# PA_Channel.net
KiCad netlist of a schematic drawn in Altium Designer
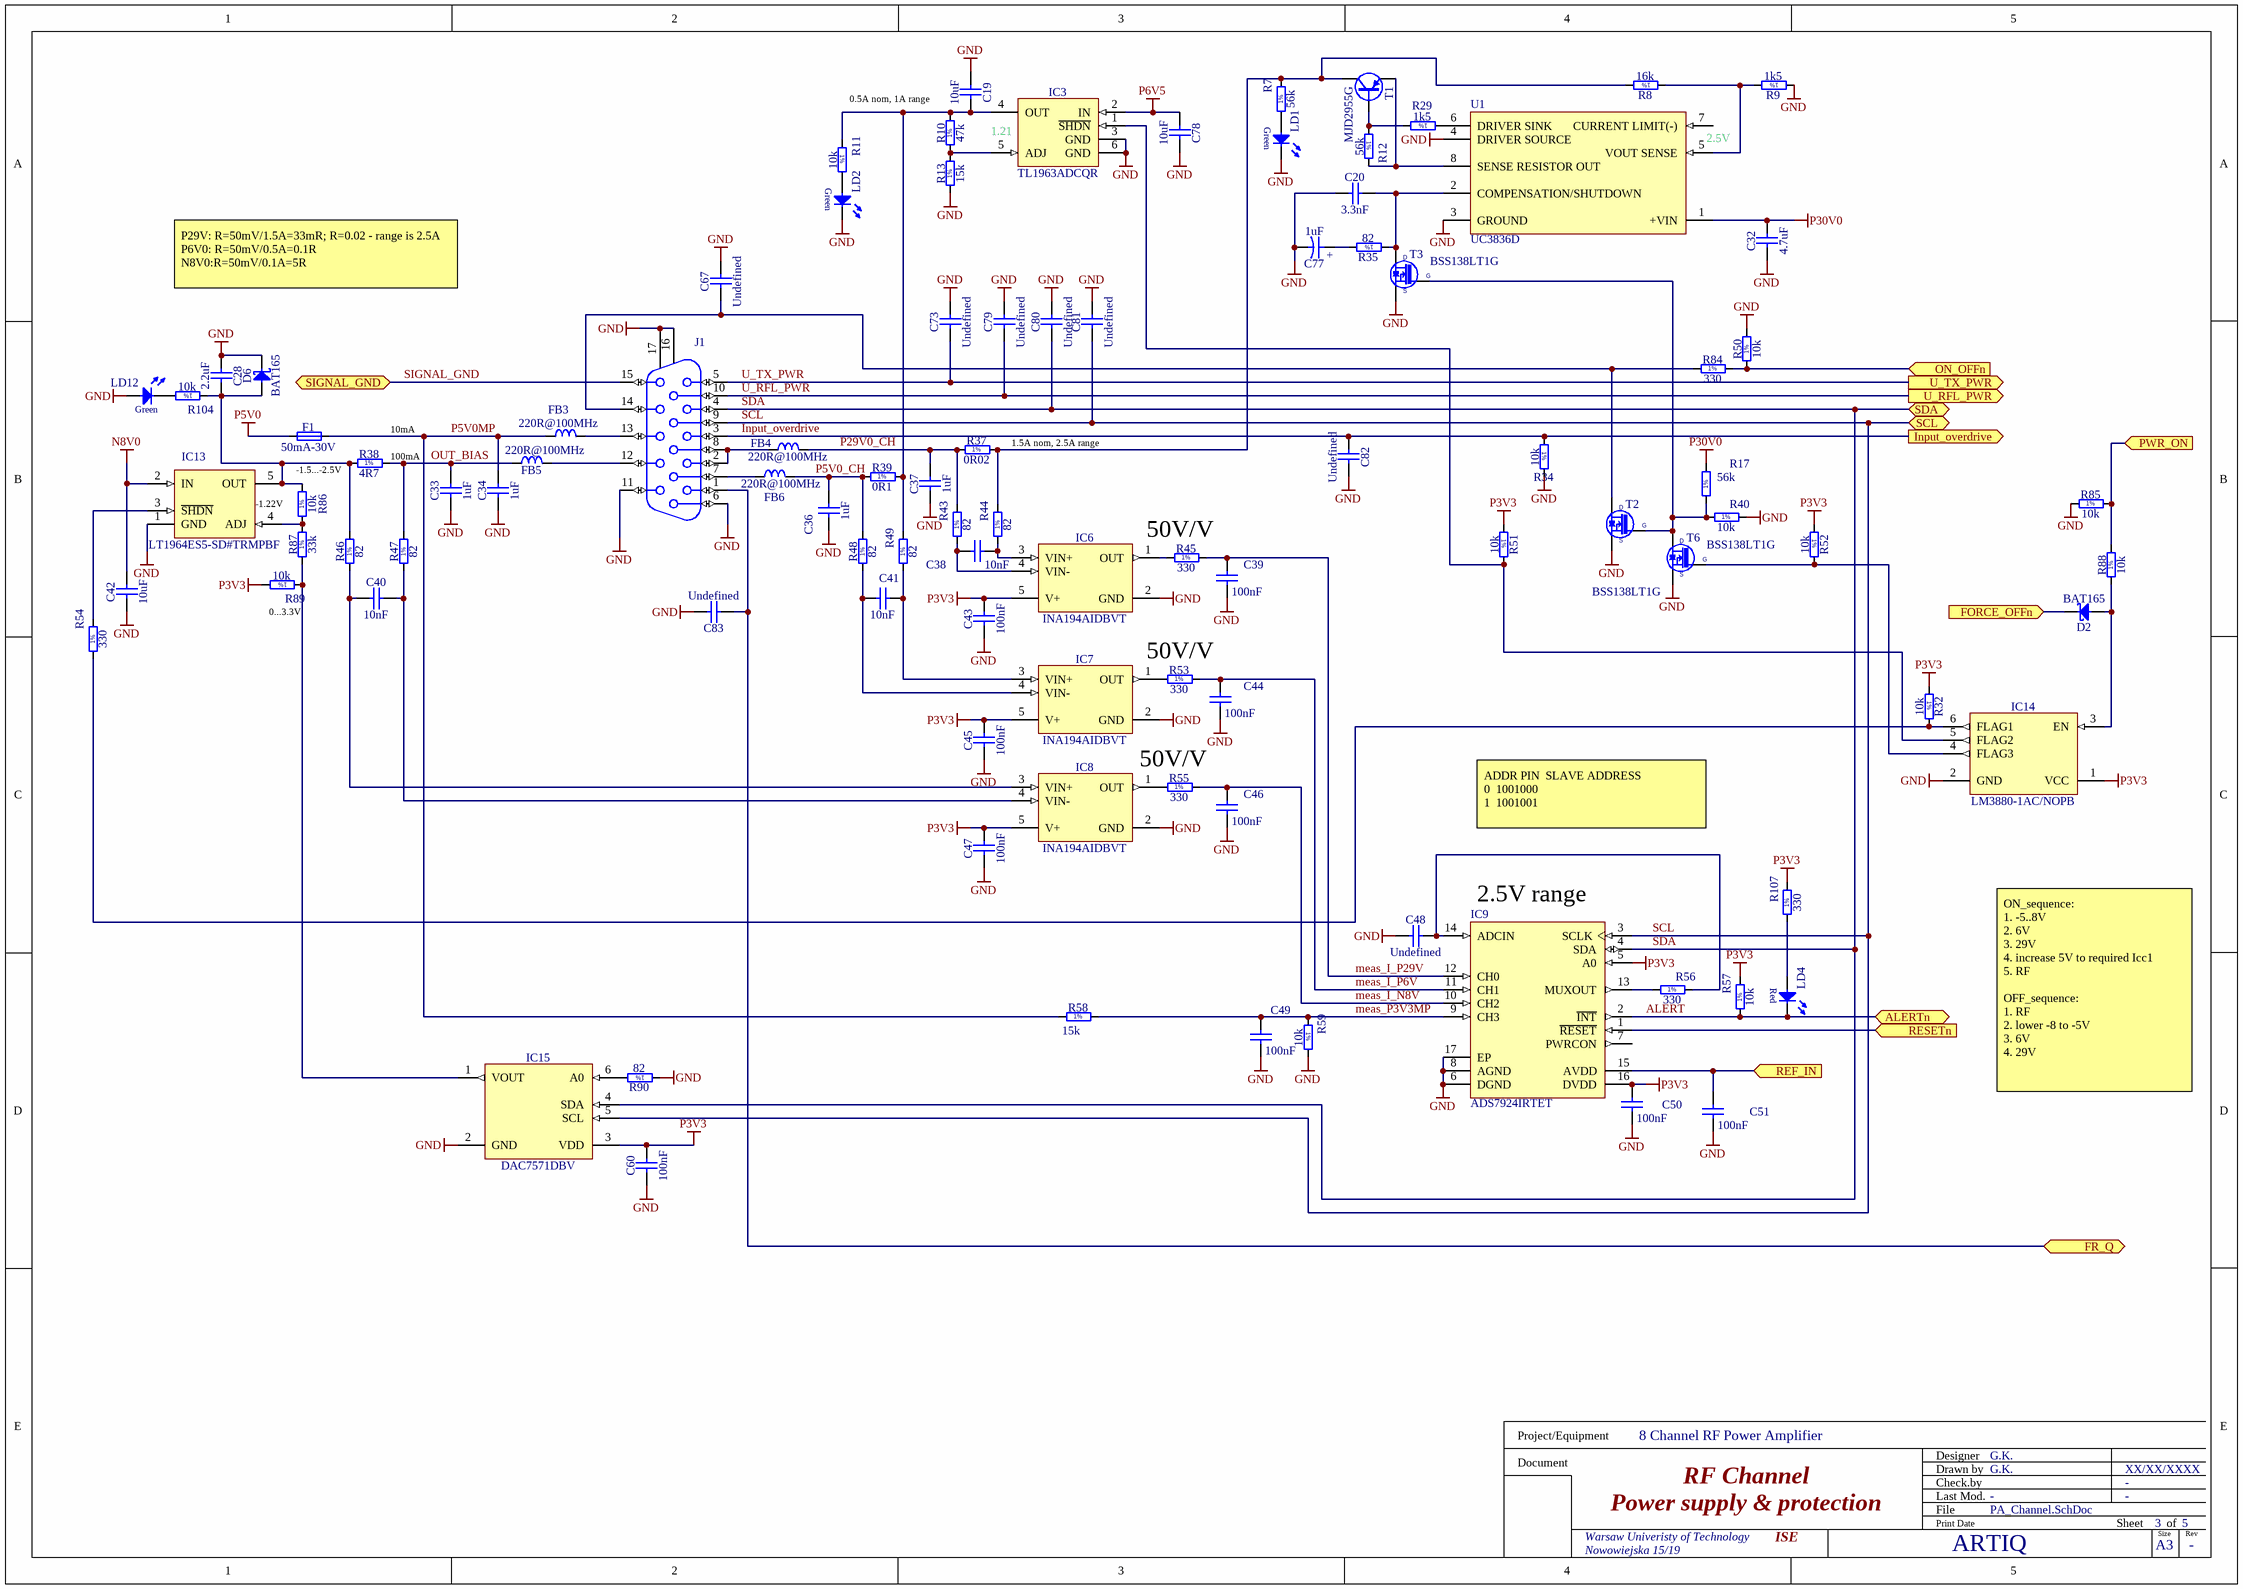
[diagram p0: PA_Channel.SchDoc]

(export (version "E")
  (design (tool "Eeschema 10.0.6"))
  (components
    (comp (ref "C19")
      (value "10uF")
      (footprint "CAPC2012X135N")
      (description "Non-polarised capacitor")
      (fields (field (name "PART NUMBER") "CC0805_10UF_16V_10%_X5R") (field (name "VOLTAGE") "16V"))
      (libsource (lib "Capacitors") (part "Capacitor - non polarized"))
    )
    (comp (ref "C20")
      (value "3.3nF")
      (footprint "CAPC1005X55N")
      (description "Non-polarised capacitor")
      (fields (field (name "PART NUMBER") "CC0402_3.3NF_50V_10%_X7R") (field (name "VOLTAGE") "50V"))
      (libsource (lib "Capacitors") (part "Capacitor - non polarized"))
    )
    (comp (ref "C28")
      (value "2.2uF")
      (footprint "CAPC1608X87N")
      (description "Non-polarised capacitor")
      (fields (field (name "PART NUMBER") "CC0603_2.2UF_16V_10%_X5R") (field (name "VOLTAGE") "16V"))
      (libsource (lib "Capacitors") (part "Capacitor - non polarized"))
    )
    (comp (ref "C32")
      (value "4.7uF")
      (footprint "CAPC3216X180N")
      (description "Non-polarised capacitor")
      (fields (field (name "PART NUMBER") "CC1206_4.7UF_50V_+80%-20%_Y5V") (field (name "VOLTAGE") "50V"))
      (libsource (lib "Capacitors") (part "Capacitor - non polarized"))
    )
    (comp (ref "C33")
      (value "1uF")
      (footprint "CAPC2012X110N")
      (description "Non-polarised capacitor")
      (fields (field (name "PART NUMBER") "CC0805_1UF_50V_10%_X7R") (field (name "VOLTAGE") "50V"))
      (libsource (lib "Capacitors") (part "Capacitor - non polarized"))
    )
    (comp (ref "C34")
      (value "1uF")
      (footprint "CAPC2012X110N")
      (description "Non-polarised capacitor")
      (fields (field (name "PART NUMBER") "CC0805_1UF_50V_10%_X7R") (field (name "VOLTAGE") "50V"))
      (libsource (lib "Capacitors") (part "Capacitor - non polarized"))
    )
    (comp (ref "C36")
      (value "1uF")
      (footprint "CAPC2012X110N")
      (description "Non-polarised capacitor")
      (fields (field (name "PART NUMBER") "CC0805_1UF_50V_10%_X7R") (field (name "VOLTAGE") "50V"))
      (libsource (lib "Capacitors") (part "Capacitor - non polarized"))
    )
    (comp (ref "C37")
      (value "1uF")
      (footprint "CAPC2012X110N")
      (description "Non-polarised capacitor")
      (fields (field (name "PART NUMBER") "CC0805_1UF_50V_10%_X7R") (field (name "VOLTAGE") "50V"))
      (libsource (lib "Capacitors") (part "Capacitor - non polarized"))
    )
    (comp (ref "C38")
      (value "10nF")
      (footprint "CAPC1608X87N")
      (description "Non-polarised capacitor")
      (fields (field (name "PART NUMBER") "CC0603_10NF_50V_5%_C0G") (field (name "VOLTAGE") "50V"))
      (libsource (lib "Capacitors") (part "Capacitor - non polarized"))
    )
    (comp (ref "C39")
      (value "100nF")
      (footprint "CAPC1005X55N")
      (description "Non-polarised capacitor")
      (fields (field (name "PART NUMBER") "CC0402_100NF_16V_10%_X7R") (field (name "VOLTAGE") "16V"))
      (libsource (lib "Capacitors") (part "Capacitor - non polarized"))
    )
    (comp (ref "C40")
      (value "10nF")
      (footprint "CAPC1608X87N")
      (description "Non-polarised capacitor")
      (fields (field (name "PART NUMBER") "CC0603_10NF_50V_5%_C0G") (field (name "VOLTAGE") "50V"))
      (libsource (lib "Capacitors") (part "Capacitor - non polarized"))
    )
    (comp (ref "C41")
      (value "10nF")
      (footprint "CAPC1608X87N")
      (description "Non-polarised capacitor")
      (fields (field (name "PART NUMBER") "CC0603_10NF_50V_5%_C0G") (field (name "VOLTAGE") "50V"))
      (libsource (lib "Capacitors") (part "Capacitor - non polarized"))
    )
    (comp (ref "C42")
      (value "10uF")
      (footprint "CAPC3216X140N")
      (description "Non-polarised capacitor")
      (fields (field (name "PART NUMBER") "CC1206_10UF_16V_10%_X7R") (field (name "VOLTAGE") "16V"))
      (libsource (lib "Capacitors") (part "Capacitor - non polarized"))
    )
    (comp (ref "C43")
      (value "100nF")
      (footprint "CAPC1005X55N")
      (description "Non-polarised capacitor")
      (fields (field (name "PART NUMBER") "CC0402_100NF_16V_10%_X7R") (field (name "VOLTAGE") "16V"))
      (libsource (lib "Capacitors") (part "Capacitor - non polarized"))
    )
    (comp (ref "C44")
      (value "100nF")
      (footprint "CAPC1005X55N")
      (description "Non-polarised capacitor")
      (fields (field (name "PART NUMBER") "CC0402_100NF_16V_10%_X7R") (field (name "VOLTAGE") "16V"))
      (libsource (lib "Capacitors") (part "Capacitor - non polarized"))
    )
    (comp (ref "C45")
      (value "100nF")
      (footprint "CAPC1005X55N")
      (description "Non-polarised capacitor")
      (fields (field (name "PART NUMBER") "CC0402_100NF_16V_10%_X7R") (field (name "VOLTAGE") "16V"))
      (libsource (lib "Capacitors") (part "Capacitor - non polarized"))
    )
    (comp (ref "C46")
      (value "100nF")
      (footprint "CAPC1005X55N")
      (description "Non-polarised capacitor")
      (fields (field (name "PART NUMBER") "CC0402_100NF_16V_10%_X7R") (field (name "VOLTAGE") "16V"))
      (libsource (lib "Capacitors") (part "Capacitor - non polarized"))
    )
    (comp (ref "C47")
      (value "100nF")
      (footprint "CAPC1005X55N")
      (description "Non-polarised capacitor")
      (fields (field (name "PART NUMBER") "CC0402_100NF_16V_10%_X7R") (field (name "VOLTAGE") "16V"))
      (libsource (lib "Capacitors") (part "Capacitor - non polarized"))
    )
    (comp (ref "C48")
      (value "Undefined")
      (footprint "CAPC1005X55N")
      (description "Non-polarised capacitor")
      (fields (field (name "PART NUMBER") "CC0402_NO-VALUE"))
      (libsource (lib "Capacitors") (part "Capacitor - non polarized"))
    )
    (comp (ref "C49")
      (value "100nF")
      (footprint "CAPC1005X55N")
      (description "Non-polarised capacitor")
      (fields (field (name "PART NUMBER") "CC0402_100NF_16V_10%_X7R") (field (name "VOLTAGE") "16V"))
      (libsource (lib "Capacitors") (part "Capacitor - non polarized"))
    )
    (comp (ref "C50")
      (value "100nF")
      (footprint "CAPC1005X55N")
      (description "Non-polarised capacitor")
      (fields (field (name "PART NUMBER") "CC0402_100NF_16V_10%_X7R") (field (name "VOLTAGE") "16V"))
      (libsource (lib "Capacitors") (part "Capacitor - non polarized"))
    )
    (comp (ref "C51")
      (value "100nF")
      (footprint "CAPC1005X55N")
      (description "Non-polarised capacitor")
      (fields (field (name "PART NUMBER") "CC0402_100NF_16V_10%_X7R") (field (name "VOLTAGE") "16V"))
      (libsource (lib "Capacitors") (part "Capacitor - non polarized"))
    )
    (comp (ref "C60")
      (value "100nF")
      (footprint "CAPC1005X55N")
      (description "Non-polarised capacitor")
      (fields (field (name "PART NUMBER") "CC0402_100NF_16V_10%_X7R") (field (name "VOLTAGE") "16V"))
      (libsource (lib "Capacitors") (part "Capacitor - non polarized"))
    )
    (comp (ref "C67")
      (value "Undefined")
      (footprint "CAPC1005X55N")
      (description "Non-polarised capacitor")
      (fields (field (name "PART NUMBER") "CC0402_NO-VALUE"))
      (libsource (lib "Capacitors") (part "Capacitor - non polarized"))
    )
    (comp (ref "C73")
      (value "Undefined")
      (footprint "CAPC1005X55N")
      (description "Non-polarised capacitor")
      (fields (field (name "PART NUMBER") "CC0402_NO-VALUE"))
      (libsource (lib "Capacitors") (part "Capacitor - non polarized"))
    )
    (comp (ref "C77")
      (value "1uF")
      (footprint "CAPMP3216X180N")
      (description "Polarised capacitor")
      (fields (field (name "PART NUMBER") "CTE3216-18_1UF_16V_10%") (field (name "VOLTAGE") "16V"))
      (libsource (lib "Capacitors") (part "Capacitor - polarized"))
    )
    (comp (ref "C78")
      (value "10uF")
      (footprint "CAPC2012X135N")
      (description "Non-polarised capacitor")
      (fields (field (name "PART NUMBER") "CC0805_10UF_16V_10%_X5R") (field (name "VOLTAGE") "16V"))
      (libsource (lib "Capacitors") (part "Capacitor - non polarized"))
    )
    (comp (ref "C79")
      (value "Undefined")
      (footprint "CAPC1005X55N")
      (description "Non-polarised capacitor")
      (fields (field (name "PART NUMBER") "CC0402_NO-VALUE"))
      (libsource (lib "Capacitors") (part "Capacitor - non polarized"))
    )
    (comp (ref "C80")
      (value "Undefined")
      (footprint "CAPC1005X55N")
      (description "Non-polarised capacitor")
      (fields (field (name "PART NUMBER") "CC0402_NO-VALUE"))
      (libsource (lib "Capacitors") (part "Capacitor - non polarized"))
    )
    (comp (ref "C81")
      (value "Undefined")
      (footprint "CAPC1005X55N")
      (description "Non-polarised capacitor")
      (fields (field (name "PART NUMBER") "CC0402_NO-VALUE"))
      (libsource (lib "Capacitors") (part "Capacitor - non polarized"))
    )
    (comp (ref "C82")
      (value "Undefined")
      (footprint "CAPC1005X55N")
      (description "Non-polarised capacitor")
      (fields (field (name "PART NUMBER") "CC0402_NO-VALUE"))
      (libsource (lib "Capacitors") (part "Capacitor - non polarized"))
    )
    (comp (ref "C83")
      (value "Undefined")
      (footprint "CAPC1005X55N")
      (description "Non-polarised capacitor")
      (fields (field (name "PART NUMBER") "CC0402_NO-VALUE"))
      (libsource (lib "Capacitors") (part "Capacitor - non polarized"))
    )
    (comp (ref "D2")
      (value "BAT165")
      (footprint "SOD2512X110N")
      (description "Schottky Diode")
      (fields (field (name "VOLTAGE") "40V") (field (name "POWER") "750mA"))
      (libsource (lib "ICs And Semiconductors") (part "Diode Schottky"))
    )
    (comp (ref "D6")
      (value "BAT165")
      (footprint "SOD2512X110N")
      (description "Schottky Diode")
      (fields (field (name "VOLTAGE") "40V") (field (name "POWER") "750mA"))
      (libsource (lib "ICs And Semiconductors") (part "Diode Schottky"))
    )
    (comp (ref "F1")
      (value "50mA-30V")
      (footprint "FUSRC3226X85N")
      (description "Fuse")
      (fields
        (field (name "PART NUMBER") "FUSR1210_TYCO-MICROSMD005F")
        (field (name "MANUFACTURER") "TYCO ELECTRONICS")
      )
      (libsource (lib "Eletro-mechanical") (part "Fuse"))
    )
    (comp (ref "FB3")
      (value "220R@100MHz")
      (footprint "INDC2012X105N")
      (description "Inductor")
      (fields (field (name "PART NUMBER") "IND0805_MURATA_BLM21PG221SN1D") (field (name "POWER") "2A"))
      (libsource (lib "Inductors & Transformers") (part "Inductor"))
    )
    (comp (ref "FB4")
      (value "220R@100MHz")
      (footprint "INDC2012X105N")
      (description "Inductor")
      (fields (field (name "PART NUMBER") "IND0805_MURATA_BLM21PG221SN1D") (field (name "POWER") "2A"))
      (libsource (lib "Inductors & Transformers") (part "Inductor"))
    )
    (comp (ref "FB5")
      (value "220R@100MHz")
      (footprint "INDC2012X105N")
      (description "Inductor")
      (fields (field (name "PART NUMBER") "IND0805_MURATA_BLM21PG221SN1D") (field (name "POWER") "2A"))
      (libsource (lib "Inductors & Transformers") (part "Inductor"))
    )
    (comp (ref "FB6")
      (value "220R@100MHz")
      (footprint "INDC2012X105N")
      (description "Inductor")
      (fields (field (name "PART NUMBER") "IND0805_MURATA_BLM21PG221SN1D") (field (name "POWER") "2A"))
      (libsource (lib "Inductors & Transformers") (part "Inductor"))
    )
    (comp (ref "IC3")
      (value "TL1963ADCQR")
      (footprint "SOT127P700X180-6N")
      (description "1.2V to 20V, 1.5A, Fast Transient Response, Low Noise, LDO Adjustable Regulator")
      (fields (field (name "MANUFACTURER") "TEXAS INSTRUMENTS"))
      (libsource (lib "ICs And Semiconductors") (part "TL1963ADCQR"))
    )
    (comp (ref "IC6")
      (value "INA194AIDBVT")
      (footprint "SOT95P280X145-5N")
      (description "Current Shunt Monitor -16V to +80V Common-Mode Range")
      (fields (field (name "MANUFACTURER") "TEXAS INSTRUMENTS"))
      (libsource (lib "ICs And Semiconductors") (part "INA194"))
    )
    (comp (ref "IC7")
      (value "INA194AIDBVT")
      (footprint "SOT95P280X145-5N")
      (description "Current Shunt Monitor -16V to +80V Common-Mode Range")
      (fields (field (name "MANUFACTURER") "TEXAS INSTRUMENTS"))
      (libsource (lib "ICs And Semiconductors") (part "INA194"))
    )
    (comp (ref "IC8")
      (value "INA194AIDBVT")
      (footprint "SOT95P280X145-5N")
      (description "Current Shunt Monitor -16V to +80V Common-Mode Range")
      (fields (field (name "MANUFACTURER") "TEXAS INSTRUMENTS"))
      (libsource (lib "ICs And Semiconductors") (part "INA194"))
    )
    (comp (ref "IC9")
      (value "ADS7924IRTET")
      (footprint "TI-RTE16-1700X1700TP_V")
      (fields (field (name "MANUFACTURER") "Texas Instruments"))
      (libsource (lib "Altium Content Vault") (part "CMP-0003-02162-1"))
    )
    (comp (ref "IC13")
      (value "LT1964ES5-SD#TRMPBF")
      (footprint "SOT95P280X100-5N")
      (description "200mA, Low Noise, Low Dropout Negative Micropower Regulator")
      (fields (field (name "MANUFACTURER") "LINEAR TECHNOLOGY"))
      (libsource (lib "ICs And Semiconductors") (part "LT1964-SD"))
    )
    (comp (ref "IC14")
      (value "LM3880-1AC/NOPB")
      (footprint "SOT95P280X145-6N")
      (description "Simple Power Sequencer")
      (fields (field (name "MANUFACTURER") "TEXAS INSTRUMENTS"))
      (libsource (lib "ICs And Semiconductors") (part "LM3880"))
    )
    (comp (ref "IC15")
      (value "DAC7571DBV")
      (footprint "SOT95P280X145-6N")
      (description "+2.7 V to +5.5 V, I2C Interface (Receive Only), Voltage Output, 12-Bit Digital-To-Analog Converter")
      (fields (field (name "MANUFACTURER") "TEXAS INSTRUMENTS"))
      (libsource (lib "ICs And Semiconductors") (part "DAC7571"))
    )
    (comp (ref "J1")
      (value "HD-Sub")
      (footprint "TYCO_1932144-1")
      (description "Connector High Density D-sub 15 Female")
      (fields (field (name "PART NUMBER") "TYCO_1932144-1") (field (name "MANUFACTURER") "TYCO ELECTRONICS"))
      (libsource (lib "LIBRARY_SCH") (part "CON_DB15_V_F_1932144-1"))
    )
    (comp (ref "LD1")
      (value "Green")
      (footprint "LED_KINGBRIGHT_KPH-1608CGCK")
      (description "LED Green 1C 2A")
      (fields
        (field (name "PART NUMBER") "LED_KINGBRIGHT_KPH-1608CGCK")
        (field (name "MANUFACTURER") "KINGBRIGHT")
      )
      (libsource (lib "ICs And Semiconductors") (part "LED Green 1C 2A"))
    )
    (comp (ref "LD2")
      (value "Green")
      (footprint "LED_KINGBRIGHT_KPH-1608CGCK")
      (description "LED Green 1C 2A")
      (fields
        (field (name "PART NUMBER") "LED_KINGBRIGHT_KPH-1608CGCK")
        (field (name "MANUFACTURER") "KINGBRIGHT")
      )
      (libsource (lib "ICs And Semiconductors") (part "LED Green 1C 2A"))
    )
    (comp (ref "LD4")
      (value "Hyper Red")
      (footprint "LED_KINGBRIGHT_KPH-1608SURCK")
      (description "LED Red 1C 2A")
      (fields
        (field (name "PART NUMBER") "LED_KINGBRIGHT_KPH-1608SURCK")
        (field (name "MANUFACTURER") "KINGBRIGHT")
      )
      (libsource (lib "ICs And Semiconductors") (part "LED Red 1C 2A"))
    )
    (comp (ref "LD12")
      (value "Green")
      (footprint "LED_KINGBRIGHT_KPH-1608CGCK")
      (description "LED Green 1C 2A")
      (fields
        (field (name "PART NUMBER") "LED_KINGBRIGHT_KPH-1608CGCK")
        (field (name "MANUFACTURER") "KINGBRIGHT")
      )
      (libsource (lib "ICs And Semiconductors") (part "LED Green 1C 2A"))
    )
    (comp (ref "R7")
      (value "56k")
      (footprint "RESC1608X55N")
      (description "Resistor - 1%")
      (fields (field (name "PART NUMBER") "R0603_56K_1%_0.1W_100PPM") (field (name "POWER") "0.1W"))
      (libsource (lib "Resistors") (part "Resistor - 1%"))
    )
    (comp (ref "R8")
      (value "16k")
      (footprint "RESC1608X55N")
      (description "Resistor - 1%")
      (fields (field (name "PART NUMBER") "R0603_16K_1%_0.1W_100PPM") (field (name "POWER") "0.1W"))
      (libsource (lib "Resistors") (part "Resistor - 1%"))
    )
    (comp (ref "R9")
      (value "1k5")
      (footprint "RESC1608X55N")
      (description "Resistor - 1%")
      (fields (field (name "PART NUMBER") "R0603_1K5_1%_0.1W_100PPM") (field (name "POWER") "0.1W"))
      (libsource (lib "Resistors") (part "Resistor - 1%"))
    )
    (comp (ref "R10")
      (value "47k")
      (footprint "RESC1005X40N")
      (description "Resistor - 1%")
      (fields (field (name "PART NUMBER") "R0402_47K_1%_0.0625W_100PPM") (field (name "POWER") "0.0625W"))
      (libsource (lib "Resistors") (part "Resistor - 1%"))
    )
    (comp (ref "R11")
      (value "10k")
      (footprint "RESC1005X40N")
      (description "Resistor - 1%")
      (fields (field (name "PART NUMBER") "R0402_10K_1%_0.0625W_100PPM") (field (name "POWER") "0.0625W"))
      (libsource (lib "Resistors") (part "Resistor - 1%"))
    )
    (comp (ref "R12")
      (value "56k")
      (footprint "RESC1608X55N")
      (description "Resistor - 1%")
      (fields (field (name "PART NUMBER") "R0603_56K_1%_0.1W_100PPM") (field (name "POWER") "0.1W"))
      (libsource (lib "Resistors") (part "Resistor - 1%"))
    )
    (comp (ref "R13")
      (value "15k")
      (footprint "RESC1005X40N")
      (description "Resistor - 1%")
      (fields (field (name "PART NUMBER") "R0402_15K_1%_0.0625W_100PPM") (field (name "POWER") "0.0625W"))
      (libsource (lib "Resistors") (part "Resistor - 1%"))
    )
    (comp (ref "R17")
      (value "56k")
      (footprint "RESC1608X55N")
      (description "Resistor - 1%")
      (fields (field (name "PART NUMBER") "R0603_56K_1%_0.1W_100PPM") (field (name "POWER") "0.1W"))
      (libsource (lib "Resistors") (part "Resistor - 1%"))
    )
    (comp (ref "R29")
      (value "1k5")
      (footprint "RESC1608X55N")
      (description "Resistor - 1%")
      (fields (field (name "PART NUMBER") "R0603_1K5_1%_0.1W_100PPM") (field (name "POWER") "0.1W"))
      (libsource (lib "Resistors") (part "Resistor - 1%"))
    )
    (comp (ref "R32")
      (value "10k")
      (footprint "RESC1005X40N")
      (description "Resistor - 1%")
      (fields (field (name "PART NUMBER") "R0402_10K_1%_0.0625W_100PPM") (field (name "POWER") "0.0625W"))
      (libsource (lib "Resistors") (part "Resistor - 1%"))
    )
    (comp (ref "R34")
      (value "10k")
      (footprint "RESC1005X40N")
      (description "Resistor - 1%")
      (fields (field (name "PART NUMBER") "R0402_10K_1%_0.0625W_100PPM") (field (name "POWER") "0.0625W"))
      (libsource (lib "Resistors") (part "Resistor - 1%"))
    )
    (comp (ref "R35")
      (value "82")
      (footprint "RESC1005X40N")
      (description "Resistor - 1%")
      (fields (field (name "PART NUMBER") "R0402_82R_1%_0.0625W_100PPM") (field (name "POWER") "0.0625W"))
      (libsource (lib "Resistors") (part "Resistor - 1%"))
    )
    (comp (ref "R37")
      (value "0R02")
      (footprint "RESC3216X80N")
      (description "Resistor - 1%")
      (fields (field (name "PART NUMBER") "R1206_0R02_1%_1W_150PPM") (field (name "POWER") "1W"))
      (libsource (lib "Resistors") (part "Resistor - 1%"))
    )
    (comp (ref "R38")
      (value "4R7")
      (footprint "RESC3216X65N")
      (description "Resistor - 1%")
      (fields (field (name "PART NUMBER") "R1206_4R7_1%_0.25W_200PPM") (field (name "POWER") "0.25W"))
      (libsource (lib "Resistors") (part "Resistor - 1%"))
    )
    (comp (ref "R39")
      (value "0R1")
      (footprint "RESC3216X65N")
      (description "Resistor - 1%")
      (fields
        (field (name "PART NUMBER") "R1206_0R1_1%_0.25W_100PPM_YAGEO_PT")
        (field (name "POWER") "0.25W")
      )
      (libsource (lib "Resistors") (part "Resistor - 1%"))
    )
    (comp (ref "R40")
      (value "10k")
      (footprint "RESC1005X40N")
      (description "Resistor - 1%")
      (fields (field (name "PART NUMBER") "R0402_10K_1%_0.0625W_100PPM") (field (name "POWER") "0.0625W"))
      (libsource (lib "Resistors") (part "Resistor - 1%"))
    )
    (comp (ref "R43")
      (value "82")
      (footprint "RESC1005X40N")
      (description "Resistor - 1%")
      (fields (field (name "PART NUMBER") "R0402_82R_1%_0.0625W_100PPM") (field (name "POWER") "0.0625W"))
      (libsource (lib "Resistors") (part "Resistor - 1%"))
    )
    (comp (ref "R44")
      (value "82")
      (footprint "RESC1005X40N")
      (description "Resistor - 1%")
      (fields (field (name "PART NUMBER") "R0402_82R_1%_0.0625W_100PPM") (field (name "POWER") "0.0625W"))
      (libsource (lib "Resistors") (part "Resistor - 1%"))
    )
    (comp (ref "R45")
      (value "330")
      (footprint "RESC1608X55N")
      (description "Resistor - 1%")
      (fields (field (name "PART NUMBER") "R0603_330R_1%_0.1W_100PPM") (field (name "POWER") "0.1W"))
      (libsource (lib "Resistors") (part "Resistor - 1%"))
    )
    (comp (ref "R46")
      (value "82")
      (footprint "RESC1005X40N")
      (description "Resistor - 1%")
      (fields (field (name "PART NUMBER") "R0402_82R_1%_0.0625W_100PPM") (field (name "POWER") "0.0625W"))
      (libsource (lib "Resistors") (part "Resistor - 1%"))
    )
    (comp (ref "R47")
      (value "82")
      (footprint "RESC1005X40N")
      (description "Resistor - 1%")
      (fields (field (name "PART NUMBER") "R0402_82R_1%_0.0625W_100PPM") (field (name "POWER") "0.0625W"))
      (libsource (lib "Resistors") (part "Resistor - 1%"))
    )
    (comp (ref "R48")
      (value "82")
      (footprint "RESC1005X40N")
      (description "Resistor - 1%")
      (fields (field (name "PART NUMBER") "R0402_82R_1%_0.0625W_100PPM") (field (name "POWER") "0.0625W"))
      (libsource (lib "Resistors") (part "Resistor - 1%"))
    )
    (comp (ref "R49")
      (value "82")
      (footprint "RESC1005X40N")
      (description "Resistor - 1%")
      (fields (field (name "PART NUMBER") "R0402_82R_1%_0.0625W_100PPM") (field (name "POWER") "0.0625W"))
      (libsource (lib "Resistors") (part "Resistor - 1%"))
    )
    (comp (ref "R50")
      (value "10k")
      (footprint "RESC1005X40N")
      (description "Resistor - 1%")
      (fields (field (name "PART NUMBER") "R0402_10K_1%_0.0625W_100PPM") (field (name "POWER") "0.0625W"))
      (libsource (lib "Resistors") (part "Resistor - 1%"))
    )
    (comp (ref "R51")
      (value "10k")
      (footprint "RESC1005X40N")
      (description "Resistor - 1%")
      (fields (field (name "PART NUMBER") "R0402_10K_1%_0.0625W_100PPM") (field (name "POWER") "0.0625W"))
      (libsource (lib "Resistors") (part "Resistor - 1%"))
    )
    (comp (ref "R52")
      (value "10k")
      (footprint "RESC1005X40N")
      (description "Resistor - 1%")
      (fields (field (name "PART NUMBER") "R0402_10K_1%_0.0625W_100PPM") (field (name "POWER") "0.0625W"))
      (libsource (lib "Resistors") (part "Resistor - 1%"))
    )
    (comp (ref "R53")
      (value "330")
      (footprint "RESC1608X55N")
      (description "Resistor - 1%")
      (fields (field (name "PART NUMBER") "R0603_330R_1%_0.1W_100PPM") (field (name "POWER") "0.1W"))
      (libsource (lib "Resistors") (part "Resistor - 1%"))
    )
    (comp (ref "R54")
      (value "330")
      (footprint "RESC1608X55N")
      (description "Resistor - 1%")
      (fields (field (name "PART NUMBER") "R0603_330R_1%_0.1W_100PPM") (field (name "POWER") "0.1W"))
      (libsource (lib "Resistors") (part "Resistor - 1%"))
    )
    (comp (ref "R55")
      (value "330")
      (footprint "RESC1608X55N")
      (description "Resistor - 1%")
      (fields (field (name "PART NUMBER") "R0603_330R_1%_0.1W_100PPM") (field (name "POWER") "0.1W"))
      (libsource (lib "Resistors") (part "Resistor - 1%"))
    )
    (comp (ref "R56")
      (value "330")
      (footprint "RESC1608X55N")
      (description "Resistor - 1%")
      (fields (field (name "PART NUMBER") "R0603_330R_1%_0.1W_100PPM") (field (name "POWER") "0.1W"))
      (libsource (lib "Resistors") (part "Resistor - 1%"))
    )
    (comp (ref "R57")
      (value "10k")
      (footprint "RESC1005X40N")
      (description "Resistor - 1%")
      (fields (field (name "PART NUMBER") "R0402_10K_1%_0.0625W_100PPM") (field (name "POWER") "0.0625W"))
      (libsource (lib "Resistors") (part "Resistor - 1%"))
    )
    (comp (ref "R58")
      (value "15k")
      (footprint "RESC1005X40N")
      (description "Resistor - 1%")
      (fields (field (name "PART NUMBER") "R0402_15K_1%_0.0625W_100PPM") (field (name "POWER") "0.0625W"))
      (libsource (lib "Resistors") (part "Resistor - 1%"))
    )
    (comp (ref "R59")
      (value "10k")
      (footprint "RESC1005X40N")
      (description "Resistor - 1%")
      (fields (field (name "PART NUMBER") "R0402_10K_1%_0.0625W_100PPM") (field (name "POWER") "0.0625W"))
      (libsource (lib "Resistors") (part "Resistor - 1%"))
    )
    (comp (ref "R84")
      (value "330")
      (footprint "RESC1608X55N")
      (description "Resistor - 1%")
      (fields (field (name "PART NUMBER") "R0603_330R_1%_0.1W_100PPM") (field (name "POWER") "0.1W"))
      (libsource (lib "Resistors") (part "Resistor - 1%"))
    )
    (comp (ref "R85")
      (value "10k")
      (footprint "RESC1005X40N")
      (description "Resistor - 1%")
      (fields (field (name "PART NUMBER") "R0402_10K_1%_0.0625W_100PPM") (field (name "POWER") "0.0625W"))
      (libsource (lib "Resistors") (part "Resistor - 1%"))
    )
    (comp (ref "R86")
      (value "10k")
      (footprint "RESC1005X40N")
      (description "Resistor - 1%")
      (fields (field (name "PART NUMBER") "R0402_10K_1%_0.0625W_100PPM") (field (name "POWER") "0.0625W"))
      (libsource (lib "Resistors") (part "Resistor - 1%"))
    )
    (comp (ref "R87")
      (value "33k")
      (footprint "RESC1608X55N")
      (description "Resistor - 1%")
      (fields (field (name "PART NUMBER") "R0603_33K_1%_0.1W_100PPM") (field (name "POWER") "0.1W"))
      (libsource (lib "Resistors") (part "Resistor - 1%"))
    )
    (comp (ref "R88")
      (value "10k")
      (footprint "RESC1005X40N")
      (description "Resistor - 1%")
      (fields (field (name "PART NUMBER") "R0402_10K_1%_0.0625W_100PPM") (field (name "POWER") "0.0625W"))
      (libsource (lib "Resistors") (part "Resistor - 1%"))
    )
    (comp (ref "R89")
      (value "10k")
      (footprint "RESC1005X40N")
      (description "Resistor - 1%")
      (fields (field (name "PART NUMBER") "R0402_10K_1%_0.0625W_100PPM") (field (name "POWER") "0.0625W"))
      (libsource (lib "Resistors") (part "Resistor - 1%"))
    )
    (comp (ref "R90")
      (value "82")
      (footprint "RESC1005X40N")
      (description "Resistor - 1%")
      (fields (field (name "PART NUMBER") "R0402_82R_1%_0.0625W_100PPM") (field (name "POWER") "0.0625W"))
      (libsource (lib "Resistors") (part "Resistor - 1%"))
    )
    (comp (ref "R104")
      (value "10k")
      (footprint "RESC1005X40N")
      (description "Resistor - 1%")
      (fields (field (name "PART NUMBER") "R0402_10K_1%_0.0625W_100PPM") (field (name "POWER") "0.0625W"))
      (libsource (lib "Resistors") (part "Resistor - 1%"))
    )
    (comp (ref "R107")
      (value "330")
      (footprint "RESC1608X55N")
      (description "Resistor - 1%")
      (fields (field (name "PART NUMBER") "R0603_330R_1%_0.1W_100PPM") (field (name "POWER") "0.1W"))
      (libsource (lib "Resistors") (part "Resistor - 1%"))
    )
    (comp (ref "T1")
      (value "MJD2955G")
      (footprint "TO228P991X239-3N-R552X520")
      (description "PNP Transistor")
      (fields (field (name "MANUFACTURER") "ON SEMICONDUCTOR"))
      (libsource (lib "ICs And Semiconductors") (part "PNP B1 E2 C3"))
    )
    (comp (ref "T2")
      (value "BSS138LT1G")
      (footprint "SOT95P240X110-3N")
      (description "N-CHANNEL MOSFET WITH DIODE")
      (fields (field (name "MANUFACTURER") "ON SEMICONDUCTOR"))
      (libsource (lib "ICs And Semiconductors") (part "N-MOSFET-D 1G 2S 3D"))
    )
    (comp (ref "T3")
      (value "BSS138LT1G")
      (footprint "SOT95P240X110-3N")
      (description "N-CHANNEL MOSFET WITH DIODE")
      (fields (field (name "MANUFACTURER") "ON SEMICONDUCTOR"))
      (libsource (lib "ICs And Semiconductors") (part "N-MOSFET-D 1G 2S 3D"))
    )
    (comp (ref "T6")
      (value "BSS138LT1G")
      (footprint "SOT95P240X110-3N")
      (description "N-CHANNEL MOSFET WITH DIODE")
      (fields (field (name "MANUFACTURER") "ON SEMICONDUCTOR"))
      (libsource (lib "ICs And Semiconductors") (part "N-MOSFET-D 1G 2S 3D"))
    )
    (comp (ref "U1")
      (value "UC3836D")
      (footprint "D0008A_M")
      (fields (field (name "MANUFACTURER") "Texas Instruments"))
      (libsource (lib "Altium Content Vault") (part "CMP-0322-00047-2"))
    )
  )
  (nets
    (net (code "1") (name "/ALERT") (class "Default")
      (node (ref "IC9") (pin "2") (pinfunction "~{INT}_2") (pintype "output"))
      (node (ref "LD4") (pin "1") (pinfunction "C_1") (pintype "passive"))
      (node (ref "R57") (pin "1") (pinfunction "1_1") (pintype "passive"))
    )
    (net (code "2") (name "/FORCE_OFFn") (class "Default")
      (node (ref "D2") (pin "1") (pinfunction "C_1") (pintype "passive"))
    )
    (net (code "3") (name "/FR_Q") (class "Default")
      (node (ref "C83") (pin "1") (pinfunction "1_1") (pintype "passive"))
      (node (ref "J1") (pin "1") (pinfunction "1_1") (pintype "bidirectional"))
    )
    (net (code "4") (name "/Input_overdrive") (class "Default")
      (node (ref "C82") (pin "1") (pinfunction "1_1") (pintype "passive"))
      (node (ref "J1") (pin "3") (pinfunction "3_3") (pintype "bidirectional"))
      (node (ref "R34") (pin "1") (pinfunction "1_1") (pintype "passive"))
    )
    (net (code "5") (name "/ON_OFFn") (class "Default")
      (node (ref "R50") (pin "1") (pinfunction "1_1") (pintype "passive"))
      (node (ref "R84") (pin "2") (pinfunction "2_2") (pintype "passive"))
    )
    (net (code "6") (name "/OUT_BIAS") (class "Default")
      (node (ref "C33") (pin "2") (pinfunction "2_2") (pintype "passive"))
      (node (ref "FB5") (pin "1") (pinfunction "1_1") (pintype "passive"))
      (node (ref "R38") (pin "2") (pinfunction "2_2") (pintype "passive"))
      (node (ref "R47") (pin "2") (pinfunction "2_2") (pintype "passive"))
    )
    (net (code "7") (name "/P5V0MP") (class "Default")
      (node (ref "C34") (pin "2") (pinfunction "2_2") (pintype "passive"))
      (node (ref "F1") (pin "2") (pinfunction "2_2") (pintype "passive"))
      (node (ref "FB3") (pin "1") (pinfunction "1_1") (pintype "passive"))
      (node (ref "R58") (pin "1") (pinfunction "1_1") (pintype "passive"))
    )
    (net (code "8") (name "/P5V0_CH") (class "Default")
      (node (ref "C36") (pin "2") (pinfunction "2_2") (pintype "passive"))
      (node (ref "FB6") (pin "2") (pinfunction "2_2") (pintype "passive"))
      (node (ref "R39") (pin "1") (pinfunction "1_1") (pintype "passive"))
      (node (ref "R48") (pin "2") (pinfunction "2_2") (pintype "passive"))
    )
    (net (code "9") (name "/P29V0_CH") (class "Default")
      (node (ref "C37") (pin "2") (pinfunction "2_2") (pintype "passive"))
      (node (ref "FB4") (pin "2") (pinfunction "2_2") (pintype "passive"))
      (node (ref "R37") (pin "1") (pinfunction "1_1") (pintype "passive"))
      (node (ref "R43") (pin "2") (pinfunction "2_2") (pintype "passive"))
    )
    (net (code "10") (name "/PWR_ON") (class "Default")
      (node (ref "R85") (pin "2") (pinfunction "2_2") (pintype "passive"))
      (node (ref "R88") (pin "2") (pinfunction "2_2") (pintype "passive"))
    )
    (net (code "11") (name "/REF_IN") (class "Default")
      (node (ref "C51") (pin "1") (pinfunction "1_1") (pintype "passive"))
      (node (ref "IC9") (pin "15") (pinfunction "AVDD_15") (pintype "power_in"))
    )
    (net (code "12") (name "/RESETn") (class "Default")
      (node (ref "IC9") (pin "1") (pinfunction "~{RESET}_1") (pintype "input"))
    )
    (net (code "13") (name "/SCL") (class "Default")
      (node (ref "C81") (pin "1") (pinfunction "1_1") (pintype "passive"))
      (node (ref "IC15") (pin "5") (pinfunction "SCL_5") (pintype "input"))
      (node (ref "IC9") (pin "3") (pinfunction "SCLK_3") (pintype "input"))
      (node (ref "J1") (pin "9") (pinfunction "9_9") (pintype "bidirectional"))
    )
    (net (code "14") (name "/SDA") (class "Default")
      (node (ref "C80") (pin "1") (pinfunction "1_1") (pintype "passive"))
      (node (ref "IC15") (pin "4") (pinfunction "SDA_4") (pintype "input"))
      (node (ref "IC9") (pin "4") (pinfunction "SDA_4") (pintype "bidirectional"))
      (node (ref "J1") (pin "4") (pinfunction "4_4") (pintype "bidirectional"))
    )
    (net (code "15") (name "/SIGNAL_GND") (class "Default")
      (node (ref "J1") (pin "15") (pinfunction "15_15") (pintype "bidirectional"))
    )
    (net (code "16") (name "/U_RFL_PWR") (class "Default")
      (node (ref "C79") (pin "1") (pinfunction "1_1") (pintype "passive"))
      (node (ref "J1") (pin "10") (pinfunction "10_10") (pintype "bidirectional"))
    )
    (net (code "17") (name "/U_TX_PWR") (class "Default")
      (node (ref "C73") (pin "1") (pinfunction "1_1") (pintype "passive"))
      (node (ref "J1") (pin "5") (pinfunction "5_5") (pintype "bidirectional"))
    )
    (net (code "18") (name "/meas_I_N8V") (class "Default")
      (node (ref "C46") (pin "1") (pinfunction "1_1") (pintype "passive"))
      (node (ref "IC9") (pin "10") (pinfunction "CH2_10") (pintype "input"))
      (node (ref "R55") (pin "2") (pinfunction "2_2") (pintype "passive"))
    )
    (net (code "19") (name "/meas_I_P6V") (class "Default")
      (node (ref "C44") (pin "1") (pinfunction "1_1") (pintype "passive"))
      (node (ref "IC9") (pin "11") (pinfunction "CH1_11") (pintype "input"))
      (node (ref "R53") (pin "2") (pinfunction "2_2") (pintype "passive"))
    )
    (net (code "20") (name "/meas_I_P29V") (class "Default")
      (node (ref "C39") (pin "1") (pinfunction "1_1") (pintype "passive"))
      (node (ref "IC9") (pin "12") (pinfunction "CH0_12") (pintype "input"))
      (node (ref "R45") (pin "2") (pinfunction "2_2") (pintype "passive"))
    )
    (net (code "21") (name "/meas_P3V3MP") (class "Default")
      (node (ref "C49") (pin "1") (pinfunction "1_1") (pintype "passive"))
      (node (ref "IC9") (pin "9") (pinfunction "CH3_9") (pintype "input"))
      (node (ref "R58") (pin "2") (pinfunction "2_2") (pintype "passive"))
      (node (ref "R59") (pin "1") (pinfunction "1_1") (pintype "passive"))
    )
    (net (code "22") (name "GND") (class "Default")
      (node (ref "C19") (pin "1") (pinfunction "1_1") (pintype "passive"))
      (node (ref "C20") (pin "1") (pinfunction "1_1") (pintype "passive"))
      (node (ref "C28") (pin "1") (pinfunction "1_1") (pintype "passive"))
      (node (ref "C32") (pin "1") (pinfunction "1_1") (pintype "passive"))
      (node (ref "C33") (pin "1") (pinfunction "1_1") (pintype "passive"))
      (node (ref "C34") (pin "1") (pinfunction "1_1") (pintype "passive"))
      (node (ref "C36") (pin "1") (pinfunction "1_1") (pintype "passive"))
      (node (ref "C37") (pin "1") (pinfunction "1_1") (pintype "passive"))
      (node (ref "C39") (pin "2") (pinfunction "2_2") (pintype "passive"))
      (node (ref "C42") (pin "1") (pinfunction "1_1") (pintype "passive"))
      (node (ref "C43") (pin "1") (pinfunction "1_1") (pintype "passive"))
      (node (ref "C44") (pin "2") (pinfunction "2_2") (pintype "passive"))
      (node (ref "C45") (pin "1") (pinfunction "1_1") (pintype "passive"))
      (node (ref "C46") (pin "2") (pinfunction "2_2") (pintype "passive"))
      (node (ref "C47") (pin "1") (pinfunction "1_1") (pintype "passive"))
      (node (ref "C48") (pin "1") (pinfunction "1_1") (pintype "passive"))
      (node (ref "C49") (pin "2") (pinfunction "2_2") (pintype "passive"))
      (node (ref "C50") (pin "2") (pinfunction "2_2") (pintype "passive"))
      (node (ref "C51") (pin "2") (pinfunction "2_2") (pintype "passive"))
      (node (ref "C60") (pin "1") (pinfunction "1_1") (pintype "passive"))
      (node (ref "C67") (pin "2") (pinfunction "2_2") (pintype "passive"))
      (node (ref "C73") (pin "2") (pinfunction "2_2") (pintype "passive"))
      (node (ref "C77") (pin "2") (pinfunction "2_2") (pintype "passive"))
      (node (ref "C78") (pin "2") (pinfunction "2_2") (pintype "passive"))
      (node (ref "C79") (pin "2") (pinfunction "2_2") (pintype "passive"))
      (node (ref "C80") (pin "2") (pinfunction "2_2") (pintype "passive"))
      (node (ref "C81") (pin "2") (pinfunction "2_2") (pintype "passive"))
      (node (ref "C82") (pin "2") (pinfunction "2_2") (pintype "passive"))
      (node (ref "C83") (pin "2") (pinfunction "2_2") (pintype "passive"))
      (node (ref "D6") (pin "1") (pinfunction "C_1") (pintype "passive"))
      (node (ref "IC13") (pin "1") (pinfunction "GND_1") (pintype "power_in"))
      (node (ref "IC14") (pin "2") (pinfunction "GND_2") (pintype "power_in"))
      (node (ref "IC15") (pin "2") (pinfunction "GND_2") (pintype "power_in"))
      (node (ref "IC3") (pin "3") (pinfunction "GND_3") (pintype "power_in"))
      (node (ref "IC3") (pin "6") (pinfunction "GND_6") (pintype "power_in"))
      (node (ref "IC6") (pin "2") (pinfunction "GND_2") (pintype "power_in"))
      (node (ref "IC7") (pin "2") (pinfunction "GND_2") (pintype "power_in"))
      (node (ref "IC8") (pin "2") (pinfunction "GND_2") (pintype "power_in"))
      (node (ref "IC9") (pin "17") (pinfunction "EP_17") (pintype "power_in"))
      (node (ref "IC9") (pin "6") (pinfunction "DGND_6") (pintype "power_in"))
      (node (ref "IC9") (pin "8") (pinfunction "AGND_8") (pintype "power_in"))
      (node (ref "J1") (pin "11") (pinfunction "11_11") (pintype "bidirectional"))
      (node (ref "J1") (pin "16") (pinfunction "16_16") (pintype "passive"))
      (node (ref "J1") (pin "17") (pinfunction "17_17") (pintype "passive"))
      (node (ref "J1") (pin "6") (pinfunction "6_6") (pintype "bidirectional"))
      (node (ref "LD1") (pin "1") (pinfunction "C_1") (pintype "passive"))
      (node (ref "LD12") (pin "2") (pinfunction "A_2") (pintype "passive"))
      (node (ref "LD2") (pin "1") (pinfunction "C_1") (pintype "passive"))
      (node (ref "R13") (pin "1") (pinfunction "1_1") (pintype "passive"))
      (node (ref "R34") (pin "2") (pinfunction "2_2") (pintype "passive"))
      (node (ref "R40") (pin "2") (pinfunction "2_2") (pintype "passive"))
      (node (ref "R50") (pin "2") (pinfunction "2_2") (pintype "passive"))
      (node (ref "R59") (pin "2") (pinfunction "2_2") (pintype "passive"))
      (node (ref "R85") (pin "1") (pinfunction "1_1") (pintype "passive"))
      (node (ref "R9") (pin "1") (pinfunction "1_1") (pintype "passive"))
      (node (ref "R90") (pin "1") (pinfunction "1_1") (pintype "passive"))
      (node (ref "T2") (pin "2") (pinfunction "S_2") (pintype "passive"))
      (node (ref "T3") (pin "2") (pinfunction "S_2") (pintype "passive"))
      (node (ref "T6") (pin "2") (pinfunction "S_2") (pintype "passive"))
      (node (ref "U1") (pin "3") (pinfunction "GROUND_3") (pintype "power_in"))
      (node (ref "U1") (pin "4") (pinfunction "DRIVER_SOURCE_4") (pintype "passive"))
    )
    (net (code "23") (name "N8V0") (class "Default")
      (node (ref "C42") (pin "2") (pinfunction "2_2") (pintype "passive"))
      (node (ref "IC13") (pin "2") (pinfunction "IN_2") (pintype "input"))
    )
    (net (code "24") (name "Net-(C77-Pad1)") (class "Default")
      (node (ref "C77") (pin "1") (pinfunction "1_1") (pintype "passive"))
      (node (ref "R35") (pin "2") (pinfunction "2_2") (pintype "passive"))
    )
    (net (code "25") (name "Net-(D2-A)") (class "Default")
      (node (ref "D2") (pin "2") (pinfunction "A_2") (pintype "passive"))
      (node (ref "IC14") (pin "3") (pinfunction "EN_3") (pintype "input"))
      (node (ref "R88") (pin "1") (pinfunction "1_1") (pintype "passive"))
    )
    (net (code "26") (name "Net-(D6-A)") (class "Default")
      (node (ref "C28") (pin "2") (pinfunction "2_2") (pintype "passive"))
      (node (ref "D6") (pin "2") (pinfunction "A_2") (pintype "passive"))
      (node (ref "IC13") (pin "5") (pinfunction "OUT_5") (pintype "power_in"))
      (node (ref "R104") (pin "1") (pinfunction "1_1") (pintype "passive"))
      (node (ref "R38") (pin "1") (pinfunction "1_1") (pintype "passive"))
      (node (ref "R46") (pin "2") (pinfunction "2_2") (pintype "passive"))
      (node (ref "R86") (pin "2") (pinfunction "2_2") (pintype "passive"))
    )
    (net (code "27") (name "Net-(FB3-Pad2)") (class "Default")
      (node (ref "FB3") (pin "2") (pinfunction "2_2") (pintype "passive"))
      (node (ref "J1") (pin "13") (pinfunction "13_13") (pintype "bidirectional"))
    )
    (net (code "28") (name "Net-(FB4-Pad1)") (class "Default")
      (node (ref "FB4") (pin "1") (pinfunction "1_1") (pintype "passive"))
      (node (ref "J1") (pin "2") (pinfunction "2_2") (pintype "bidirectional"))
      (node (ref "J1") (pin "8") (pinfunction "8_8") (pintype "bidirectional"))
    )
    (net (code "29") (name "Net-(FB5-Pad2)") (class "Default")
      (node (ref "FB5") (pin "2") (pinfunction "2_2") (pintype "passive"))
      (node (ref "J1") (pin "12") (pinfunction "12_12") (pintype "bidirectional"))
    )
    (net (code "30") (name "Net-(FB6-Pad1)") (class "Default")
      (node (ref "FB6") (pin "1") (pinfunction "1_1") (pintype "passive"))
      (node (ref "J1") (pin "7") (pinfunction "7_7") (pintype "bidirectional"))
    )
    (net (code "31") (name "Net-(IC3-ADJ)") (class "Default")
      (node (ref "IC3") (pin "5") (pinfunction "ADJ_5") (pintype "input"))
      (node (ref "R10") (pin "1") (pinfunction "1_1") (pintype "passive"))
      (node (ref "R13") (pin "2") (pinfunction "2_2") (pintype "passive"))
    )
    (net (code "32") (name "Net-(IC3-OUT)") (class "Default")
      (node (ref "C19") (pin "2") (pinfunction "2_2") (pintype "passive"))
      (node (ref "IC3") (pin "4") (pinfunction "OUT_4") (pintype "power_in"))
      (node (ref "R10") (pin "2") (pinfunction "2_2") (pintype "passive"))
      (node (ref "R11") (pin "1") (pinfunction "1_1") (pintype "passive"))
      (node (ref "R39") (pin "2") (pinfunction "2_2") (pintype "passive"))
      (node (ref "R49") (pin "2") (pinfunction "2_2") (pintype "passive"))
    )
    (net (code "33") (name "Net-(IC6-OUT)") (class "Default")
      (node (ref "IC6") (pin "1") (pinfunction "OUT_1") (pintype "output"))
      (node (ref "R45") (pin "1") (pinfunction "1_1") (pintype "passive"))
    )
    (net (code "34") (name "Net-(IC6-VIN+)") (class "Default")
      (node (ref "C38") (pin "2") (pinfunction "2_2") (pintype "passive"))
      (node (ref "IC6") (pin "3") (pinfunction "VIN+_3") (pintype "input"))
      (node (ref "R44") (pin "1") (pinfunction "1_1") (pintype "passive"))
    )
    (net (code "35") (name "Net-(IC6-VIN-)") (class "Default")
      (node (ref "C38") (pin "1") (pinfunction "1_1") (pintype "passive"))
      (node (ref "IC6") (pin "4") (pinfunction "VIN-_4") (pintype "input"))
      (node (ref "R43") (pin "1") (pinfunction "1_1") (pintype "passive"))
    )
    (net (code "36") (name "Net-(IC7-OUT)") (class "Default")
      (node (ref "IC7") (pin "1") (pinfunction "OUT_1") (pintype "output"))
      (node (ref "R53") (pin "1") (pinfunction "1_1") (pintype "passive"))
    )
    (net (code "37") (name "Net-(IC7-VIN+)") (class "Default")
      (node (ref "C41") (pin "2") (pinfunction "2_2") (pintype "passive"))
      (node (ref "IC7") (pin "3") (pinfunction "VIN+_3") (pintype "input"))
      (node (ref "R49") (pin "1") (pinfunction "1_1") (pintype "passive"))
    )
    (net (code "38") (name "Net-(IC7-VIN-)") (class "Default")
      (node (ref "C41") (pin "1") (pinfunction "1_1") (pintype "passive"))
      (node (ref "IC7") (pin "4") (pinfunction "VIN-_4") (pintype "input"))
      (node (ref "R48") (pin "1") (pinfunction "1_1") (pintype "passive"))
    )
    (net (code "39") (name "Net-(IC8-OUT)") (class "Default")
      (node (ref "IC8") (pin "1") (pinfunction "OUT_1") (pintype "output"))
      (node (ref "R55") (pin "1") (pinfunction "1_1") (pintype "passive"))
    )
    (net (code "40") (name "Net-(IC8-VIN+)") (class "Default")
      (node (ref "C40") (pin "1") (pinfunction "1_1") (pintype "passive"))
      (node (ref "IC8") (pin "3") (pinfunction "VIN+_3") (pintype "input"))
      (node (ref "R46") (pin "1") (pinfunction "1_1") (pintype "passive"))
    )
    (net (code "41") (name "Net-(IC8-VIN-)") (class "Default")
      (node (ref "C40") (pin "2") (pinfunction "2_2") (pintype "passive"))
      (node (ref "IC8") (pin "4") (pinfunction "VIN-_4") (pintype "input"))
      (node (ref "R47") (pin "1") (pinfunction "1_1") (pintype "passive"))
    )
    (net (code "42") (name "Net-(IC9-ADCIN)") (class "Default")
      (node (ref "C48") (pin "2") (pinfunction "2_2") (pintype "passive"))
      (node (ref "IC9") (pin "14") (pinfunction "ADCIN_14") (pintype "input"))
      (node (ref "R56") (pin "2") (pinfunction "2_2") (pintype "passive"))
    )
    (net (code "43") (name "Net-(IC9-MUXOUT)") (class "Default")
      (node (ref "IC9") (pin "13") (pinfunction "MUXOUT_13") (pintype "output"))
      (node (ref "R56") (pin "1") (pinfunction "1_1") (pintype "passive"))
    )
    (net (code "44") (name "Net-(IC13-ADJ)") (class "Default")
      (node (ref "IC13") (pin "4") (pinfunction "ADJ_4") (pintype "input"))
      (node (ref "R86") (pin "1") (pinfunction "1_1") (pintype "passive"))
      (node (ref "R87") (pin "2") (pinfunction "2_2") (pintype "passive"))
    )
    (net (code "45") (name "Net-(IC13-~{SHDN})") (class "Default")
      (node (ref "IC13") (pin "3") (pinfunction "~{SHDN}_3") (pintype "input"))
      (node (ref "R54") (pin "2") (pinfunction "2_2") (pintype "passive"))
    )
    (net (code "46") (name "Net-(IC14-FLAG1)") (class "Default")
      (node (ref "IC14") (pin "6") (pinfunction "FLAG1_6") (pintype "output"))
      (node (ref "R32") (pin "2") (pinfunction "2_2") (pintype "passive"))
      (node (ref "R54") (pin "1") (pinfunction "1_1") (pintype "passive"))
    )
    (net (code "47") (name "Net-(IC14-FLAG2)") (class "Default")
      (node (ref "IC14") (pin "5") (pinfunction "FLAG2_5") (pintype "output"))
      (node (ref "IC3") (pin "1") (pinfunction "~{SHDN}_1") (pintype "input"))
      (node (ref "R51") (pin "2") (pinfunction "2_2") (pintype "passive"))
    )
    (net (code "48") (name "Net-(IC14-FLAG3)") (class "Default")
      (node (ref "IC14") (pin "4") (pinfunction "FLAG3_4") (pintype "output"))
      (node (ref "R52") (pin "2") (pinfunction "2_2") (pintype "passive"))
      (node (ref "T6") (pin "1") (pinfunction "G_1") (pintype "passive"))
    )
    (net (code "49") (name "Net-(IC15-A0)") (class "Default")
      (node (ref "IC15") (pin "6") (pinfunction "A0_6") (pintype "input"))
      (node (ref "R90") (pin "2") (pinfunction "2_2") (pintype "passive"))
    )
    (net (code "50") (name "Net-(IC15-VOUT)") (class "Default")
      (node (ref "IC15") (pin "1") (pinfunction "VOUT_1") (pintype "output"))
      (node (ref "R87") (pin "1") (pinfunction "1_1") (pintype "passive"))
      (node (ref "R89") (pin "1") (pinfunction "1_1") (pintype "passive"))
    )
    (net (code "51") (name "Net-(LD1-A)") (class "Default")
      (node (ref "LD1") (pin "2") (pinfunction "A_2") (pintype "passive"))
      (node (ref "R7") (pin "1") (pinfunction "1_1") (pintype "passive"))
    )
    (net (code "52") (name "Net-(LD2-A)") (class "Default")
      (node (ref "LD2") (pin "2") (pinfunction "A_2") (pintype "passive"))
      (node (ref "R11") (pin "2") (pinfunction "2_2") (pintype "passive"))
    )
    (net (code "53") (name "Net-(LD4-A)") (class "Default")
      (node (ref "LD4") (pin "2") (pinfunction "A_2") (pintype "passive"))
      (node (ref "R107") (pin "1") (pinfunction "1_1") (pintype "passive"))
    )
    (net (code "54") (name "Net-(LD12-C)") (class "Default")
      (node (ref "LD12") (pin "1") (pinfunction "C_1") (pintype "passive"))
      (node (ref "R104") (pin "2") (pinfunction "2_2") (pintype "passive"))
    )
    (net (code "55") (name "Net-(T1-B)") (class "Default")
      (node (ref "R12") (pin "1") (pinfunction "1_1") (pintype "passive"))
      (node (ref "R29") (pin "2") (pinfunction "2_2") (pintype "passive"))
      (node (ref "T1") (pin "1") (pinfunction "B_1") (pintype "passive"))
    )
    (net (code "56") (name "Net-(T1-C)") (class "Default")
      (node (ref "R37") (pin "2") (pinfunction "2_2") (pintype "passive"))
      (node (ref "R44") (pin "2") (pinfunction "2_2") (pintype "passive"))
      (node (ref "R7") (pin "2") (pinfunction "2_2") (pintype "passive"))
      (node (ref "R8") (pin "2") (pinfunction "2_2") (pintype "passive"))
      (node (ref "T1") (pin "3") (pinfunction "C_3") (pintype "passive"))
    )
    (net (code "57") (name "Net-(T1-E)") (class "Default")
      (node (ref "R12") (pin "2") (pinfunction "2_2") (pintype "passive"))
      (node (ref "T1") (pin "2") (pinfunction "E_2") (pintype "passive"))
      (node (ref "U1") (pin "8") (pinfunction "SENSE_RESISTOR_OUT_8") (pintype "passive"))
    )
    (net (code "58") (name "Net-(T2-D)") (class "Default")
      (node (ref "C67") (pin "1") (pinfunction "1_1") (pintype "passive"))
      (node (ref "J1") (pin "14") (pinfunction "14_14") (pintype "bidirectional"))
      (node (ref "R84") (pin "1") (pinfunction "1_1") (pintype "passive"))
      (node (ref "T2") (pin "3") (pinfunction "D_3") (pintype "passive"))
    )
    (net (code "59") (name "Net-(T2-G)") (class "Default")
      (node (ref "R17") (pin "1") (pinfunction "1_1") (pintype "passive"))
      (node (ref "R40") (pin "1") (pinfunction "1_1") (pintype "passive"))
      (node (ref "T2") (pin "1") (pinfunction "G_1") (pintype "passive"))
      (node (ref "T3") (pin "1") (pinfunction "G_1") (pintype "passive"))
      (node (ref "T6") (pin "3") (pinfunction "D_3") (pintype "passive"))
    )
    (net (code "60") (name "Net-(T3-D)") (class "Default")
      (node (ref "C20") (pin "2") (pinfunction "2_2") (pintype "passive"))
      (node (ref "R35") (pin "1") (pinfunction "1_1") (pintype "passive"))
      (node (ref "T3") (pin "3") (pinfunction "D_3") (pintype "passive"))
      (node (ref "U1") (pin "2") (pinfunction "COMPENSATION/SHUTDOWN_2") (pintype "passive"))
    )
    (net (code "61") (name "Net-(U1-DRIVER_SINK)") (class "Default")
      (node (ref "R29") (pin "1") (pinfunction "1_1") (pintype "passive"))
      (node (ref "U1") (pin "6") (pinfunction "DRIVER_SINK_6") (pintype "passive"))
    )
    (net (code "62") (name "Net-(U1-VOUT_SENSE)") (class "Default")
      (node (ref "R8") (pin "1") (pinfunction "1_1") (pintype "passive"))
      (node (ref "R9") (pin "2") (pinfunction "2_2") (pintype "passive"))
      (node (ref "U1") (pin "5") (pinfunction "VOUT_SENSE_5") (pintype "input"))
    )
    (net (code "63") (name "P3V3") (class "Default")
      (node (ref "C43") (pin "2") (pinfunction "2_2") (pintype "passive"))
      (node (ref "C45") (pin "2") (pinfunction "2_2") (pintype "passive"))
      (node (ref "C47") (pin "2") (pinfunction "2_2") (pintype "passive"))
      (node (ref "C50") (pin "1") (pinfunction "1_1") (pintype "passive"))
      (node (ref "C60") (pin "2") (pinfunction "2_2") (pintype "passive"))
      (node (ref "IC14") (pin "1") (pinfunction "VCC_1") (pintype "power_in"))
      (node (ref "IC15") (pin "3") (pinfunction "VDD_3") (pintype "power_in"))
      (node (ref "IC6") (pin "5") (pinfunction "V+_5") (pintype "power_in"))
      (node (ref "IC7") (pin "5") (pinfunction "V+_5") (pintype "power_in"))
      (node (ref "IC8") (pin "5") (pinfunction "V+_5") (pintype "power_in"))
      (node (ref "IC9") (pin "16") (pinfunction "DVDD_16") (pintype "power_in"))
      (node (ref "IC9") (pin "5") (pinfunction "A0_5") (pintype "input"))
      (node (ref "R107") (pin "2") (pinfunction "2_2") (pintype "passive"))
      (node (ref "R32") (pin "1") (pinfunction "1_1") (pintype "passive"))
      (node (ref "R51") (pin "1") (pinfunction "1_1") (pintype "passive"))
      (node (ref "R52") (pin "1") (pinfunction "1_1") (pintype "passive"))
      (node (ref "R57") (pin "2") (pinfunction "2_2") (pintype "passive"))
      (node (ref "R89") (pin "2") (pinfunction "2_2") (pintype "passive"))
    )
    (net (code "64") (name "P5V0") (class "Default")
      (node (ref "F1") (pin "1") (pinfunction "1_1") (pintype "passive"))
    )
    (net (code "65") (name "P6V5") (class "Default")
      (node (ref "C78") (pin "1") (pinfunction "1_1") (pintype "passive"))
      (node (ref "IC3") (pin "2") (pinfunction "IN_2") (pintype "input"))
    )
    (net (code "66") (name "P30V0") (class "Default")
      (node (ref "C32") (pin "2") (pinfunction "2_2") (pintype "passive"))
      (node (ref "R17") (pin "2") (pinfunction "2_2") (pintype "passive"))
      (node (ref "U1") (pin "1") (pinfunction "+VIN_1") (pintype "power_in"))
    )
    (net (code "67") (name "unconnected-(IC9-PWRCON-Pad7)") (class "Default")
      (node (ref "IC9") (pin "7") (pinfunction "PWRCON_7") (pintype "output"))
    )
    (net (code "68") (name "unconnected-(U1-CURRENT_LIMIT(-)-Pad7)") (class "Default")
      (node (ref "U1") (pin "7") (pinfunction "CURRENT_LIMIT(-)_7") (pintype "input"))
    )
  )
)
